# Battery_Control.net
KiCad netlist of a schematic drawn in Altium Designer
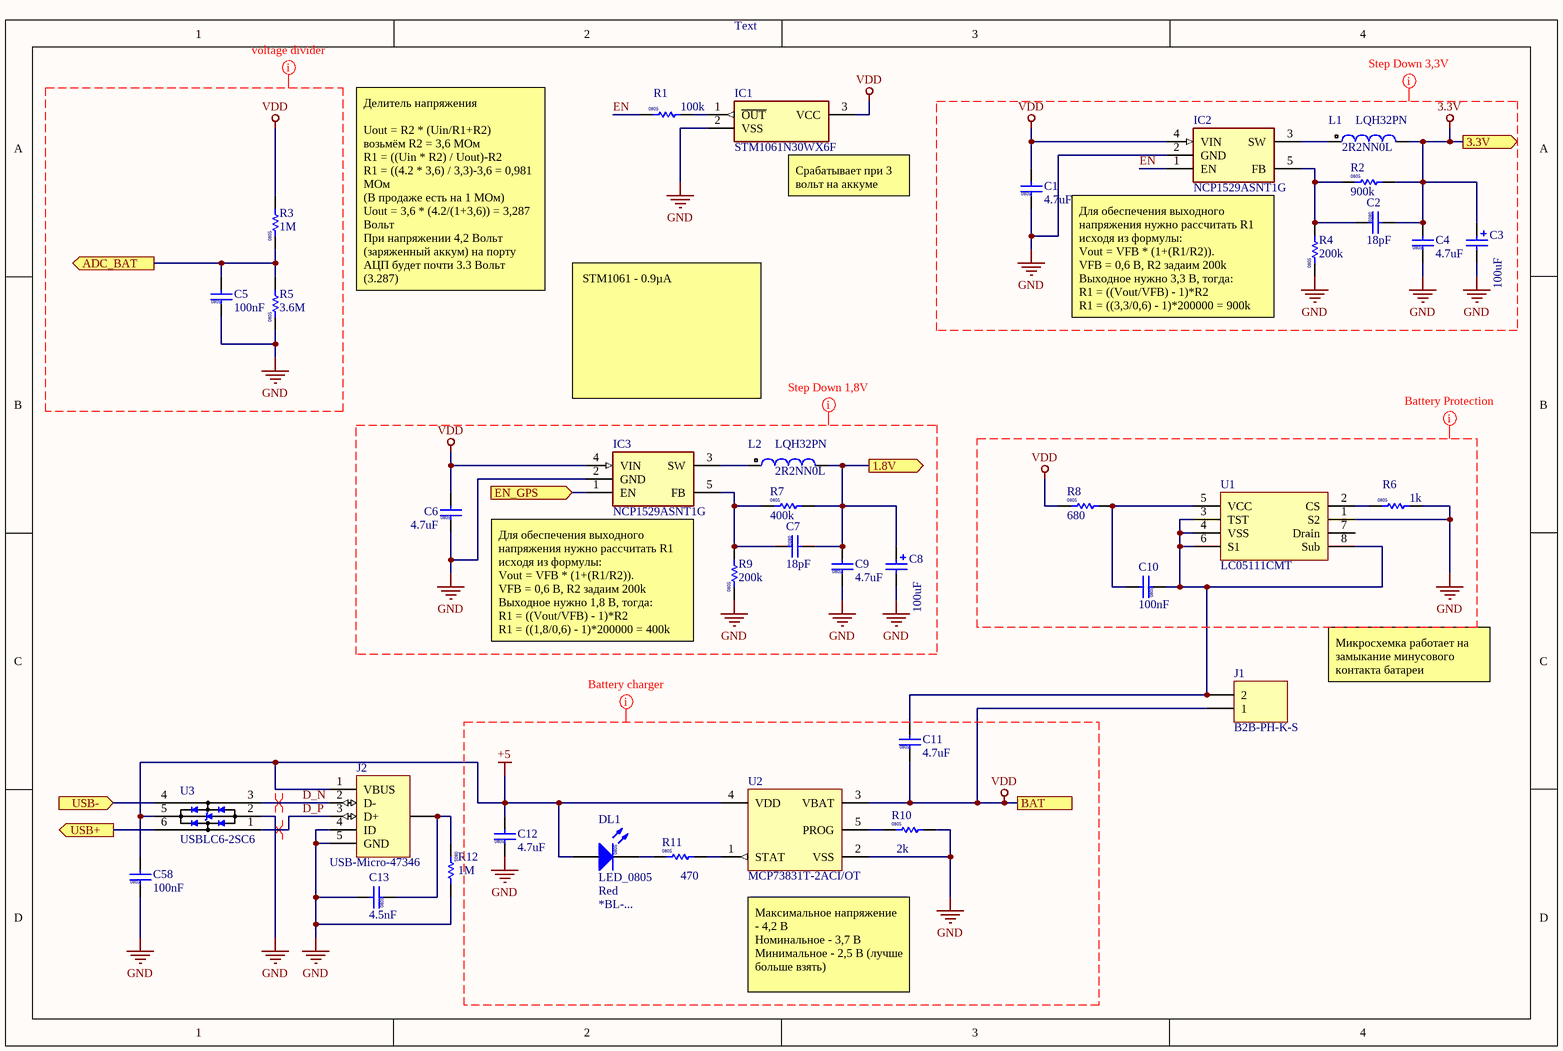
[diagram p0: Battery_Control.SchDoc]

(export (version "E")
  (design (tool "Eeschema 10.0.6"))
  (components
    (comp (ref "C1")
      (value "4.7uF")
      (footprint "CAPC2012-0805M")
      (description "Capacitor 0805")
      (fields (field (name "Comment") "CAPC_0805"))
      (libsource (lib "Passive") (part "CAPC_0805"))
    )
    (comp (ref "C2")
      (value "18pF")
      (footprint "CAPC2012-0805M")
      (description "Capacitor 0805")
      (fields (field (name "Comment") "CAPC_0805"))
      (libsource (lib "Passive") (part "CAPC_0805"))
    )
    (comp (ref "C3")
      (value "100uF")
      (footprint "ECAPC_0505")
      (description "Electrolytic Capacitor SMD 0505")
      (fields (field (name "Comment") "ECAPC_0505") (field (name "PUBLISHER") "Altium Limited"))
      (libsource (lib "Passive") (part "ECAPC_0505"))
    )
    (comp (ref "C4")
      (value "4.7uF")
      (footprint "CAPC2012-0805M")
      (description "Capacitor 0805")
      (fields (field (name "Comment") "CAPC_0805"))
      (libsource (lib "Passive") (part "CAPC_0805"))
    )
    (comp (ref "C5")
      (value "100nF")
      (footprint "CAPC2012-0805M")
      (description "Capacitor 0805")
      (fields (field (name "Comment") "CAPC_0805"))
      (libsource (lib "Passive") (part "CAPC_0805"))
    )
    (comp (ref "C6")
      (value "4.7uF")
      (footprint "CAPC2012-0805M")
      (description "Capacitor 0805")
      (fields (field (name "Comment") "CAPC_0805"))
      (libsource (lib "Passive") (part "CAPC_0805"))
    )
    (comp (ref "C7")
      (value "18pF")
      (footprint "CAPC2012-0805M")
      (description "Capacitor 0805")
      (fields (field (name "Comment") "CAPC_0805"))
      (libsource (lib "Passive") (part "CAPC_0805"))
    )
    (comp (ref "C8")
      (value "100uF")
      (footprint "ECAPC_0505")
      (description "Electrolytic Capacitor SMD 0505")
      (fields (field (name "Comment") "ECAPC_0505") (field (name "PUBLISHER") "Altium Limited"))
      (libsource (lib "Passive") (part "ECAPC_0505"))
    )
    (comp (ref "C9")
      (value "4.7uF")
      (footprint "CAPC2012-0805M")
      (description "Capacitor 0805")
      (fields (field (name "Comment") "CAPC_0805"))
      (libsource (lib "Passive") (part "CAPC_0805"))
    )
    (comp (ref "C10")
      (value "100nF")
      (footprint "CAPC2012-0805M")
      (description "Capacitor 0805")
      (fields (field (name "Comment") "CAPC_0805"))
      (libsource (lib "Passive") (part "CAPC_0805"))
    )
    (comp (ref "C11")
      (value "4.7uF")
      (footprint "CAPC2012-0805M")
      (description "Capacitor 0805")
      (fields (field (name "Comment") "CAPC_0805"))
      (libsource (lib "Passive") (part "CAPC_0805"))
    )
    (comp (ref "C12")
      (value "4.7uF")
      (footprint "CAPC2012-0805M")
      (description "Capacitor 0805")
      (fields (field (name "Comment") "CAPC_0805"))
      (libsource (lib "Passive") (part "CAPC_0805"))
    )
    (comp (ref "C13")
      (value "4.5nF")
      (footprint "CAPC2012-0805M")
      (description "Capacitor 0805")
      (fields (field (name "Comment") "CAPC_0805"))
      (libsource (lib "Passive") (part "CAPC_0805"))
    )
    (comp (ref "C58")
      (value "100nF")
      (footprint "CAPC2012-0805M")
      (description "Capacitor 0805")
      (fields (field (name "Comment") "CAPC_0805"))
      (libsource (lib "Passive") (part "CAPC_0805"))
    )
    (comp (ref "DL1")
      (value "LED_0805")
      (footprint "DIODEC2012-0805")
      (description "LED 0805")
      (fields (field (name "COLOR") "Red") (field (name "PART NUMBER") "*BL-..."))
      (libsource (lib "Discrete") (part "LED_0805"))
    )
    (comp (ref "IC1")
      (value "STM1061N30WX6F")
      (footprint "Bogdanov:SOT103P237X112-3N")
      (description "Integrated Circuit")
      (fields
        (field (name "MANUFACTURER_PART_NUMBER") "STM1061N34WX6F")
        (field (name "MOUSER PART NUMBER") "511-STM1061N34WX6F")
      )
      (libsource (lib "Bogdanov") (part "STM1061N34WX6F"))
    )
    (comp (ref "IC2")
      (value "NCP1529ASNT1G")
      (footprint "SOT95P275X110-5N")
      (description "Integrated Circuit")
      (fields
        (field (name "MOUSER PART NUMBER") "863-NCP1529ASNT1G")
        (field (name "RS PART NUMBER") "8023161P")
      )
      (libsource (lib "Bogdanov") (part "NCP1529ASNT1G"))
    )
    (comp (ref "IC3")
      (value "NCP1529ASNT1G")
      (footprint "SOT95P275X110-5N")
      (description "Integrated Circuit")
      (fields
        (field (name "MOUSER PART NUMBER") "863-NCP1529ASNT1G")
        (field (name "RS PART NUMBER") "8023161P")
      )
      (libsource (lib "Bogdanov") (part "NCP1529ASNT1G"))
    )
    (comp (ref "J1")
      (value "B2B-PH-K-S")
      (footprint "B2B-PH-K-S")
      (description "B2B-PH-K-S 2.0 mm pitrch header PCB straight")
      (libsource (lib "Connectors") (part "B2B-PH-K-S"))
    )
    (comp (ref "J2")
      (value "USB-Micro-47346")
      (footprint "USB_micro_B")
      (description "Micro USB B Molex 47346")
      (libsource (lib "Connectors") (part "USB-Micro-47346"))
    )
    (comp (ref "L1")
      (value "LQH32PN")
      (footprint "LQH32PN_N")
      (description "LQH32PN Murata inductor")
      (fields (field (name "ALTIUM_VALUE") "2R2NN0L") (field (name "PUBLISHER") "Altium Limited"))
      (libsource (lib "Passive") (part "LQH32PN"))
    )
    (comp (ref "L2")
      (value "LQH32PN")
      (footprint "LQH32PN_N")
      (description "LQH32PN Murata inductor")
      (fields (field (name "ALTIUM_VALUE") "2R2NN0L") (field (name "PUBLISHER") "Altium Limited"))
      (libsource (lib "Passive") (part "LQH32PN"))
    )
    (comp (ref "R1")
      (value "100k")
      (footprint "RESC2012-0805M")
      (description "Resistor 0805")
      (fields (field (name "Comment") "RESC_0805"))
      (libsource (lib "Passive") (part "RESC_0805"))
    )
    (comp (ref "R2")
      (value "900k")
      (footprint "RESC2012-0805M")
      (description "Resistor 0805")
      (fields (field (name "Comment") "RESC_0805"))
      (libsource (lib "Passive") (part "RESC_0805"))
    )
    (comp (ref "R3")
      (value "1M")
      (footprint "RESC2012-0805M")
      (description "Resistor 0805")
      (fields (field (name "Comment") "RESC_0805"))
      (libsource (lib "Passive") (part "RESC_0805"))
    )
    (comp (ref "R4")
      (value "200k")
      (footprint "RESC2012-0805M")
      (description "Resistor 0805")
      (fields (field (name "Comment") "RESC_0805"))
      (libsource (lib "Passive") (part "RESC_0805"))
    )
    (comp (ref "R5")
      (value "3.6M")
      (footprint "RESC2012-0805M")
      (description "Resistor 0805")
      (fields (field (name "Comment") "RESC_0805"))
      (libsource (lib "Passive") (part "RESC_0805"))
    )
    (comp (ref "R6")
      (value "1k")
      (footprint "RESC2012-0805M")
      (description "Resistor 0805")
      (fields (field (name "Comment") "RESC_0805"))
      (libsource (lib "Passive") (part "RESC_0805"))
    )
    (comp (ref "R7")
      (value "400k")
      (footprint "RESC2012-0805M")
      (description "Resistor 0805")
      (fields (field (name "Comment") "RESC_0805"))
      (libsource (lib "Passive") (part "RESC_0805"))
    )
    (comp (ref "R8")
      (value "680")
      (footprint "RESC2012-0805M")
      (description "Resistor 0805")
      (fields (field (name "Comment") "RESC_0805"))
      (libsource (lib "Passive") (part "RESC_0805"))
    )
    (comp (ref "R9")
      (value "200k")
      (footprint "RESC2012-0805M")
      (description "Resistor 0805")
      (fields (field (name "Comment") "RESC_0805"))
      (libsource (lib "Passive") (part "RESC_0805"))
    )
    (comp (ref "R10")
      (value "2k")
      (footprint "RESC2012-0805M")
      (description "Resistor 0805")
      (fields (field (name "Comment") "RESC_0805"))
      (libsource (lib "Passive") (part "RESC_0805"))
    )
    (comp (ref "R11")
      (value "470")
      (footprint "RESC2012-0805M")
      (description "Resistor 0805")
      (fields (field (name "Comment") "RESC_0805"))
      (libsource (lib "Passive") (part "RESC_0805"))
    )
    (comp (ref "R12")
      (value "1M")
      (footprint "RESC2012-0805M")
      (description "Resistor 0805")
      (fields (field (name "Comment") "RESC_0805"))
      (libsource (lib "Passive") (part "RESC_0805"))
    )
    (comp (ref "U1")
      (value "LC05111CMT")
      (footprint "WDFN6 2.6x4.0, 0.65P")
      (description "Защита Li-On от перезаряда переразряда")
      (libsource (lib "Bogdanov") (part "LC05111CMT"))
    )
    (comp (ref "U2")
      (value "MCP73831T-2ACI/OT")
      (footprint "SOT-23-OT5_N")
      (fields (field (name "MANUFACTURER") "Microchip"))
      (libsource (lib "Microchip Power Management Battery Management") (part "MCP73831T-2ACI/OT"))
    )
    (comp (ref "U3")
      (value "USBLC6-2SC6")
      (footprint "SOT23-6L_ST")
      (description "USBLC6-2SC6 ESD protection diodes assembly")
      (libsource (lib "Discrete") (part "USBLC6-2SC6"))
    )
  )
  (nets
    (net (code "1") (name "+5") (class "Default")
      (node (ref "C12") (pin "2") (pinfunction "2_2") (pintype "passive"))
      (node (ref "C58") (pin "2") (pinfunction "2_2") (pintype "passive"))
      (node (ref "DL1") (pin "1") (pinfunction "A_1") (pintype "passive"))
      (node (ref "J2") (pin "1") (pinfunction "VBUS_1") (pintype "power_in"))
      (node (ref "U2") (pin "4") (pinfunction "VDD_4") (pintype "power_in"))
      (node (ref "U3") (pin "5") (pinfunction "Vbus_5") (pintype "passive"))
    )
    (net (code "2") (name "/1.8V") (class "Default")
      (node (ref "C7") (pin "2") (pinfunction "2_2") (pintype "passive"))
      (node (ref "C8") (pin "1") (pinfunction "1_1") (pintype "passive"))
      (node (ref "C9") (pin "2") (pinfunction "2_2") (pintype "passive"))
      (node (ref "L2") (pin "2") (pinfunction "2_2") (pintype "passive"))
      (node (ref "R7") (pin "2") (pinfunction "2_2") (pintype "passive"))
    )
    (net (code "3") (name "/ADC_BAT") (class "Default")
      (node (ref "C5") (pin "2") (pinfunction "2_2") (pintype "passive"))
      (node (ref "R3") (pin "1") (pinfunction "1_1") (pintype "passive"))
      (node (ref "R5") (pin "2") (pinfunction "2_2") (pintype "passive"))
    )
    (net (code "4") (name "/D_N") (class "Default")
      (node (ref "J2") (pin "2") (pinfunction "D-_2") (pintype "bidirectional"))
      (node (ref "U3") (pin "3") (pinfunction "IO2_3") (pintype "passive"))
    )
    (net (code "5") (name "/D_P") (class "Default")
      (node (ref "J2") (pin "3") (pinfunction "D+_3") (pintype "bidirectional"))
      (node (ref "U3") (pin "1") (pinfunction "IO1_1") (pintype "passive"))
    )
    (net (code "6") (name "/EN") (class "Default")
      (node (ref "IC2") (pin "1") (pinfunction "EN_1") (pintype "passive"))
      (node (ref "R1") (pin "1") (pinfunction "1_1") (pintype "passive"))
    )
    (net (code "7") (name "/EN_GPS") (class "Default")
      (node (ref "IC3") (pin "1") (pinfunction "EN_1") (pintype "passive"))
    )
    (net (code "8") (name "/USB+") (class "Default")
      (node (ref "U3") (pin "6") (pinfunction "IO1_6") (pintype "passive"))
    )
    (net (code "9") (name "/USB-") (class "Default")
      (node (ref "U3") (pin "4") (pinfunction "IO2_4") (pintype "passive"))
    )
    (net (code "10") (name "3.3V") (class "Default")
      (node (ref "C2") (pin "2") (pinfunction "2_2") (pintype "passive"))
      (node (ref "C3") (pin "1") (pinfunction "1_1") (pintype "passive"))
      (node (ref "C4") (pin "2") (pinfunction "2_2") (pintype "passive"))
      (node (ref "L1") (pin "2") (pinfunction "2_2") (pintype "passive"))
      (node (ref "R2") (pin "2") (pinfunction "2_2") (pintype "passive"))
    )
    (net (code "11") (name "GND") (class "Default")
      (node (ref "C1") (pin "1") (pinfunction "1_1") (pintype "passive"))
      (node (ref "C12") (pin "1") (pinfunction "1_1") (pintype "passive"))
      (node (ref "C13") (pin "2") (pinfunction "2_2") (pintype "passive"))
      (node (ref "C3") (pin "2") (pinfunction "2_2") (pintype "passive"))
      (node (ref "C4") (pin "1") (pinfunction "1_1") (pintype "passive"))
      (node (ref "C5") (pin "1") (pinfunction "1_1") (pintype "passive"))
      (node (ref "C58") (pin "1") (pinfunction "1_1") (pintype "passive"))
      (node (ref "C6") (pin "1") (pinfunction "1_1") (pintype "passive"))
      (node (ref "C8") (pin "2") (pinfunction "2_2") (pintype "passive"))
      (node (ref "C9") (pin "1") (pinfunction "1_1") (pintype "passive"))
      (node (ref "IC1") (pin "2") (pinfunction "VSS_2") (pintype "power_in"))
      (node (ref "IC2") (pin "2") (pinfunction "GND_2") (pintype "power_in"))
      (node (ref "IC3") (pin "2") (pinfunction "GND_2") (pintype "power_in"))
      (node (ref "J2") (pin "4") (pinfunction "ID_4") (pintype "passive"))
      (node (ref "J2") (pin "5") (pinfunction "GND_5") (pintype "power_in"))
      (node (ref "R10") (pin "2") (pinfunction "2_2") (pintype "passive"))
      (node (ref "R12") (pin "2") (pinfunction "2_2") (pintype "passive"))
      (node (ref "R4") (pin "1") (pinfunction "1_1") (pintype "passive"))
      (node (ref "R5") (pin "1") (pinfunction "1_1") (pintype "passive"))
      (node (ref "R6") (pin "2") (pinfunction "2_2") (pintype "passive"))
      (node (ref "R9") (pin "1") (pinfunction "1_1") (pintype "passive"))
      (node (ref "U1") (pin "1") (pinfunction "S2_1") (pintype "passive"))
      (node (ref "U2") (pin "2") (pinfunction "VSS_2") (pintype "power_in"))
      (node (ref "U3") (pin "2") (pinfunction "GND_2") (pintype "passive"))
    )
    (net (code "12") (name "Net-(DL1-K)") (class "Default")
      (node (ref "DL1") (pin "2") (pinfunction "K_2") (pintype "passive"))
      (node (ref "R11") (pin "1") (pinfunction "1_1") (pintype "passive"))
    )
    (net (code "13") (name "Net-(IC1-~{OUT})") (class "Default")
      (node (ref "IC1") (pin "1") (pinfunction "~{OUT}_1") (pintype "output"))
      (node (ref "R1") (pin "2") (pinfunction "2_2") (pintype "passive"))
    )
    (net (code "14") (name "Net-(IC2-FB)") (class "Default")
      (node (ref "C2") (pin "1") (pinfunction "1_1") (pintype "passive"))
      (node (ref "IC2") (pin "5") (pinfunction "FB_5") (pintype "passive"))
      (node (ref "R2") (pin "1") (pinfunction "1_1") (pintype "passive"))
      (node (ref "R4") (pin "2") (pinfunction "2_2") (pintype "passive"))
    )
    (net (code "15") (name "Net-(IC2-SW)") (class "Default")
      (node (ref "IC2") (pin "3") (pinfunction "SW_3") (pintype "passive"))
      (node (ref "L1") (pin "1") (pinfunction "1_1") (pintype "passive"))
    )
    (net (code "16") (name "Net-(IC3-FB)") (class "Default")
      (node (ref "C7") (pin "1") (pinfunction "1_1") (pintype "passive"))
      (node (ref "IC3") (pin "5") (pinfunction "FB_5") (pintype "passive"))
      (node (ref "R7") (pin "1") (pinfunction "1_1") (pintype "passive"))
      (node (ref "R9") (pin "2") (pinfunction "2_2") (pintype "passive"))
    )
    (net (code "17") (name "Net-(IC3-SW)") (class "Default")
      (node (ref "IC3") (pin "3") (pinfunction "SW_3") (pintype "passive"))
      (node (ref "L2") (pin "1") (pinfunction "1_1") (pintype "passive"))
    )
    (net (code "18") (name "Net-(J2-SHLD)") (class "Default")
      (node (ref "C13") (pin "1") (pinfunction "1_1") (pintype "passive"))
      (node (ref "J2") (pin "SHIELD") (pinfunction "SHLD_SHIELD") (pintype "passive"))
      (node (ref "R12") (pin "1") (pinfunction "1_1") (pintype "passive"))
    )
    (net (code "19") (name "Net-(U1-CS)") (class "Default")
      (node (ref "R6") (pin "1") (pinfunction "1_1") (pintype "passive"))
      (node (ref "U1") (pin "2") (pinfunction "CS_2") (pintype "passive"))
    )
    (net (code "20") (name "Net-(U1-S1)") (class "Default")
      (node (ref "C10") (pin "1") (pinfunction "1_1") (pintype "passive"))
      (node (ref "C11") (pin "2") (pinfunction "2_2") (pintype "passive"))
      (node (ref "J1") (pin "2") (pinfunction "2_2") (pintype "passive"))
      (node (ref "U1") (pin "3") (pinfunction "TST_3") (pintype "passive"))
      (node (ref "U1") (pin "4") (pinfunction "VSS_4") (pintype "passive"))
      (node (ref "U1") (pin "6") (pinfunction "S1_6") (pintype "passive"))
      (node (ref "U1") (pin "8") (pinfunction "Sub_8") (pintype "passive"))
    )
    (net (code "21") (name "Net-(U1-VCC)") (class "Default")
      (node (ref "C10") (pin "2") (pinfunction "2_2") (pintype "passive"))
      (node (ref "R8") (pin "2") (pinfunction "2_2") (pintype "passive"))
      (node (ref "U1") (pin "5") (pinfunction "VCC_5") (pintype "passive"))
    )
    (net (code "22") (name "Net-(U2-PROG)") (class "Default")
      (node (ref "R10") (pin "1") (pinfunction "1_1") (pintype "passive"))
      (node (ref "U2") (pin "5") (pinfunction "PROG_5") (pintype "passive"))
    )
    (net (code "23") (name "Net-(U2-STAT)") (class "Default")
      (node (ref "R11") (pin "2") (pinfunction "2_2") (pintype "passive"))
      (node (ref "U2") (pin "1") (pinfunction "STAT_1") (pintype "output"))
    )
    (net (code "24") (name "VDD") (class "Default")
      (node (ref "C1") (pin "2") (pinfunction "2_2") (pintype "passive"))
      (node (ref "C11") (pin "1") (pinfunction "1_1") (pintype "passive"))
      (node (ref "C6") (pin "2") (pinfunction "2_2") (pintype "passive"))
      (node (ref "IC1") (pin "3") (pinfunction "VCC_3") (pintype "power_in"))
      (node (ref "IC2") (pin "4") (pinfunction "VIN_4") (pintype "input"))
      (node (ref "IC3") (pin "4") (pinfunction "VIN_4") (pintype "input"))
      (node (ref "J1") (pin "1") (pinfunction "1_1") (pintype "passive"))
      (node (ref "R3") (pin "2") (pinfunction "2_2") (pintype "passive"))
      (node (ref "R8") (pin "1") (pinfunction "1_1") (pintype "passive"))
      (node (ref "U2") (pin "3") (pinfunction "VBAT_3") (pintype "power_in"))
    )
    (net (code "25") (name "unconnected-(U1-Drain-Pad7)") (class "Default")
      (node (ref "U1") (pin "7") (pinfunction "Drain_7") (pintype "passive"))
    )
  )
)
